# Rover-1_Power_Supply.net
KiCad netlist of a schematic drawn in EAGLE
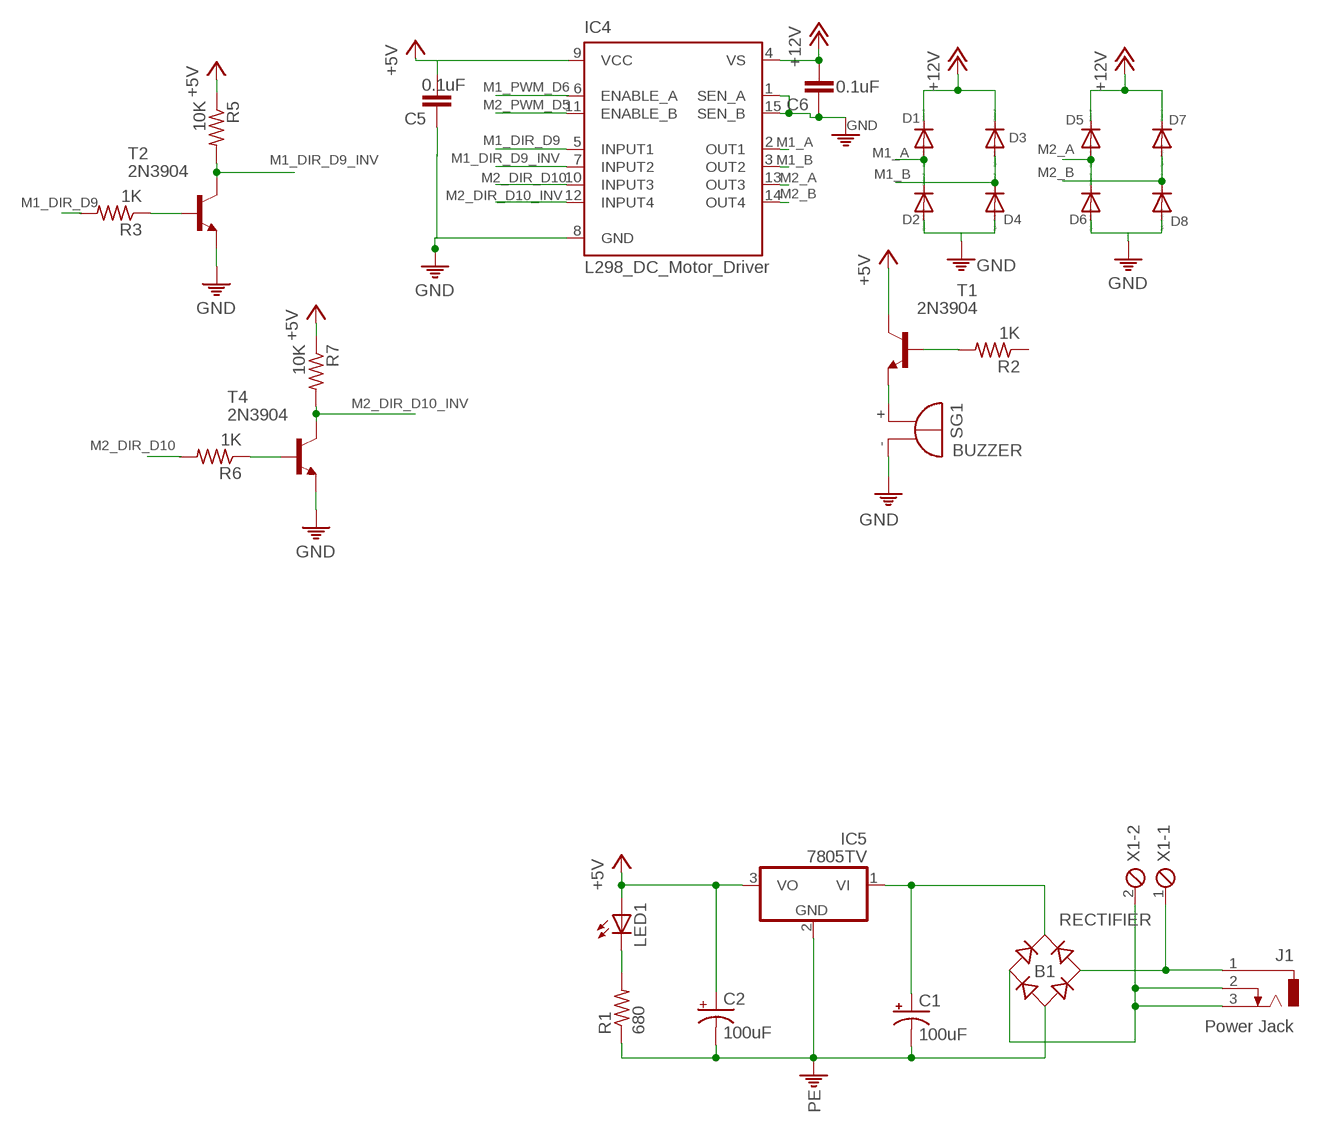
[diagram p0: schematic, sheet 1]

(export (version "E")
  (design (tool "Eeschema 10.0.6"))
  (components
    (comp (ref "B1")
      (value "RECTIFIER")
      (footprint "eagle-import:RB1A")
      (libsource (lib "eagle-import") (part "RB1A"))
    )
    (comp (ref "C1")
      (value "100uF")
      (footprint "eagle-import:E5-8,5")
      (libsource (lib "eagle-import") (part "CPOL-USE5-8.5"))
    )
    (comp (ref "C2")
      (value "100uF")
      (footprint "eagle-import:E5-8,5")
      (libsource (lib "eagle-import") (part "CPOL-USE5-8.5"))
    )
    (comp (ref "C5")
      (value "0.1uF")
      (footprint "eagle-import:C025-024X044")
      (libsource (lib "eagle-import") (part "C-EU025-024X044"))
    )
    (comp (ref "C6")
      (value "0.1uF")
      (footprint "eagle-import:C025-024X044")
      (libsource (lib "eagle-import") (part "C-EU025-024X044"))
    )
    (comp (ref "D1")
      (value "DIODE-D-2.5")
      (footprint "eagle-import:D-2.5")
      (libsource (lib "eagle-import") (part "DIODE-D-2.5"))
    )
    (comp (ref "D2")
      (value "DIODE-D-2.5")
      (footprint "eagle-import:D-2.5")
      (libsource (lib "eagle-import") (part "DIODE-D-2.5"))
    )
    (comp (ref "D3")
      (value "DIODE-D-2.5")
      (footprint "eagle-import:D-2.5")
      (libsource (lib "eagle-import") (part "DIODE-D-2.5"))
    )
    (comp (ref "D4")
      (value "DIODE-D-2.5")
      (footprint "eagle-import:D-2.5")
      (libsource (lib "eagle-import") (part "DIODE-D-2.5"))
    )
    (comp (ref "D5")
      (value "DIODE-D-2.5")
      (footprint "eagle-import:D-2.5")
      (libsource (lib "eagle-import") (part "DIODE-D-2.5"))
    )
    (comp (ref "D6")
      (value "DIODE-D-2.5")
      (footprint "eagle-import:D-2.5")
      (libsource (lib "eagle-import") (part "DIODE-D-2.5"))
    )
    (comp (ref "D7")
      (value "DIODE-D-2.5")
      (footprint "eagle-import:D-2.5")
      (libsource (lib "eagle-import") (part "DIODE-D-2.5"))
    )
    (comp (ref "D8")
      (value "DIODE-D-2.5")
      (footprint "eagle-import:D-2.5")
      (libsource (lib "eagle-import") (part "DIODE-D-2.5"))
    )
    (comp (ref "IC4")
      (value "L298_DC_Motor_Driver")
      (footprint "eagle-import:MULTIWATT-15")
      (fields (field (name "MPN") "L298N"))
      (libsource (lib "eagle-import") (part "L298"))
    )
    (comp (ref "IC5")
      (value "7805TV")
      (footprint "eagle-import:TO220V")
      (libsource (lib "eagle-import") (part "78TV05"))
    )
    (comp (ref "J1")
      (value "Power Jack")
      (footprint "eagle-import:ROVER-PW-JACL")
      (libsource (lib "eagle-import") (part "DCJ0303"))
    )
    (comp (ref "LED1")
      (value "LED3MM")
      (footprint "eagle-import:LED3MM")
      (libsource (lib "eagle-import") (part "LED3MM"))
    )
    (comp (ref "R1")
      (value "680")
      (footprint "eagle-import:0204_5")
      (libsource (lib "eagle-import") (part "R-US_0204/5"))
    )
    (comp (ref "R2")
      (value "1K")
      (footprint "eagle-import:0204_5")
      (libsource (lib "eagle-import") (part "R-US_0204/5"))
    )
    (comp (ref "R3")
      (value "1K")
      (footprint "eagle-import:0204_5")
      (libsource (lib "eagle-import") (part "R-US_0204/5"))
    )
    (comp (ref "R5")
      (value "10K")
      (footprint "eagle-import:0204_5")
      (libsource (lib "eagle-import") (part "R-US_0204/5"))
    )
    (comp (ref "R6")
      (value "1K")
      (footprint "eagle-import:0204_5")
      (libsource (lib "eagle-import") (part "R-US_0204/5"))
    )
    (comp (ref "R7")
      (value "10K")
      (footprint "eagle-import:0204_5")
      (libsource (lib "eagle-import") (part "R-US_0204/5"))
    )
    (comp (ref "SG1")
      (value "BUZZER")
      (footprint "eagle-import:EB2209A")
      (libsource (lib "eagle-import") (part "EB2209A"))
    )
    (comp (ref "T1")
      (value "2N3904")
      (footprint "eagle-import:TO92")
      (libsource (lib "eagle-import") (part "2N3904"))
    )
    (comp (ref "T2")
      (value "2N3904")
      (footprint "eagle-import:TO92")
      (libsource (lib "eagle-import") (part "2N3904"))
    )
    (comp (ref "T4")
      (value "2N3904")
      (footprint "eagle-import:TO92")
      (libsource (lib "eagle-import") (part "2N3904"))
    )
    (comp (ref "X1")
      (value "MPT2")
      (footprint "eagle-import:2POL254")
      (libsource (lib "eagle-import") (part "MPT2"))
    )
  )
  (nets
    (net (code "1") (name "+5V") (class "Default")
      (node (ref "C2") (pin "+") (pinfunction "+_+") (pintype "passive"))
      (node (ref "C5") (pin "2") (pinfunction "2_2") (pintype "passive"))
      (node (ref "IC5") (pin "3") (pinfunction "VO_3") (pintype "passive"))
      (node (ref "LED1") (pin "A") (pinfunction "A_A") (pintype "passive"))
      (node (ref "R5") (pin "1") (pinfunction "1_1") (pintype "passive"))
      (node (ref "R7") (pin "1") (pinfunction "1_1") (pintype "passive"))
      (node (ref "T1") (pin "1") (pinfunction "C_1") (pintype "passive"))
    )
    (net (code "2") (name "+12V") (class "Default")
      (node (ref "C6") (pin "2") (pinfunction "2_2") (pintype "passive"))
      (node (ref "D1") (pin "C") (pinfunction "C_C") (pintype "passive"))
      (node (ref "D3") (pin "C") (pinfunction "C_C") (pintype "passive"))
      (node (ref "D5") (pin "C") (pinfunction "C_C") (pintype "passive"))
      (node (ref "D7") (pin "C") (pinfunction "C_C") (pintype "passive"))
      (node (ref "IC4") (pin "4") (pinfunction "VS_4") (pintype "power_in"))
    )
    (net (code "3") (name "/M1_A") (class "Default")
      (node (ref "D1") (pin "A") (pinfunction "A_A") (pintype "passive"))
      (node (ref "D2") (pin "C") (pinfunction "C_C") (pintype "passive"))
      (node (ref "IC4") (pin "2") (pinfunction "OUT1_2") (pintype "output"))
    )
    (net (code "4") (name "/M1_B") (class "Default")
      (node (ref "D3") (pin "A") (pinfunction "A_A") (pintype "passive"))
      (node (ref "D4") (pin "C") (pinfunction "C_C") (pintype "passive"))
      (node (ref "IC4") (pin "3") (pinfunction "OUT2_3") (pintype "output"))
    )
    (net (code "5") (name "/M1_DIR_D9") (class "Default")
      (node (ref "IC4") (pin "5") (pinfunction "INPUT1_5") (pintype "input"))
    )
    (net (code "6") (name "/M1_DIR_D9_INV") (class "Default")
      (node (ref "IC4") (pin "7") (pinfunction "INPUT2_7") (pintype "input"))
      (node (ref "R5") (pin "2") (pinfunction "2_2") (pintype "passive"))
      (node (ref "T2") (pin "1") (pinfunction "C_1") (pintype "passive"))
    )
    (net (code "8") (name "/M2_A") (class "Default")
      (node (ref "D5") (pin "A") (pinfunction "A_A") (pintype "passive"))
      (node (ref "D6") (pin "C") (pinfunction "C_C") (pintype "passive"))
      (node (ref "IC4") (pin "13") (pinfunction "OUT3_13") (pintype "output"))
    )
    (net (code "9") (name "/M2_B") (class "Default")
      (node (ref "D7") (pin "A") (pinfunction "A_A") (pintype "passive"))
      (node (ref "D8") (pin "C") (pinfunction "C_C") (pintype "passive"))
      (node (ref "IC4") (pin "14") (pinfunction "OUT4_14") (pintype "output"))
    )
    (net (code "10") (name "/M2_DIR_D10") (class "Default")
      (node (ref "IC4") (pin "10") (pinfunction "INPUT3_10") (pintype "input"))
    )
    (net (code "11") (name "/M2_DIR_D10_INV") (class "Default")
      (node (ref "IC4") (pin "12") (pinfunction "INPUT4_12") (pintype "input"))
      (node (ref "R7") (pin "2") (pinfunction "2_2") (pintype "passive"))
      (node (ref "T4") (pin "1") (pinfunction "C_1") (pintype "passive"))
    )
    (net (code "12") (name "/M2_PWM_D5") (class "Default")
      (node (ref "IC4") (pin "11") (pinfunction "ENABLE_B_11") (pintype "input"))
    )
    (net (code "13") (name "/VCC") (class "Default")
      (node (ref "IC4") (pin "9") (pinfunction "VCC_9") (pintype "power_in"))
    )
    (net (code "14") (name "GND") (class "Default")
      (node (ref "B1") (pin "-") (pinfunction "-_-") (pintype "passive"))
      (node (ref "C1") (pin "-") (pinfunction "-_-") (pintype "passive"))
      (node (ref "C2") (pin "-") (pinfunction "-_-") (pintype "passive"))
      (node (ref "C6") (pin "1") (pinfunction "1_1") (pintype "passive"))
      (node (ref "D2") (pin "A") (pinfunction "A_A") (pintype "passive"))
      (node (ref "D4") (pin "A") (pinfunction "A_A") (pintype "passive"))
      (node (ref "D6") (pin "A") (pinfunction "A_A") (pintype "passive"))
      (node (ref "D8") (pin "A") (pinfunction "A_A") (pintype "passive"))
      (node (ref "IC4") (pin "1") (pinfunction "SEN_A_1") (pintype "input"))
      (node (ref "IC4") (pin "15") (pinfunction "SEN_B_15") (pintype "input"))
      (node (ref "IC4") (pin "8") (pinfunction "GND_8") (pintype "power_in"))
      (node (ref "IC5") (pin "2") (pinfunction "GND_2") (pintype "passive"))
      (node (ref "R1") (pin "1") (pinfunction "1_1") (pintype "passive"))
      (node (ref "SG1") (pin "-") (pinfunction "-_-") (pintype "passive"))
      (node (ref "T2") (pin "3") (pinfunction "E_3") (pintype "passive"))
      (node (ref "T4") (pin "3") (pinfunction "E_3") (pintype "passive"))
    )
    (net (code "15") (name "Net-(B1-PadAC1)") (class "Default")
      (node (ref "B1") (pin "AC1") (pinfunction "AC1_AC1") (pintype "passive"))
      (node (ref "J1") (pin "1") (pinfunction "1_1") (pintype "passive"))
      (node (ref "X1") (pin "1") (pinfunction "1_1") (pintype "passive"))
    )
    (net (code "16") (name "Net-(IC5-VI)") (class "Default")
      (node (ref "B1") (pin "+") (pinfunction "+_+") (pintype "passive"))
      (node (ref "C1") (pin "+") (pinfunction "+_+") (pintype "passive"))
      (node (ref "IC5") (pin "1") (pinfunction "VI_1") (pintype "input"))
    )
    (net (code "17") (name "Net-(LED1-C)") (class "Default")
      (node (ref "LED1") (pin "K") (pinfunction "C_K") (pintype "passive"))
      (node (ref "R1") (pin "2") (pinfunction "2_2") (pintype "passive"))
    )
    (net (code "18") (name "Net-(T1-E)") (class "Default")
      (node (ref "SG1") (pin "+") (pinfunction "+_+") (pintype "passive"))
      (node (ref "T1") (pin "3") (pinfunction "E_3") (pintype "passive"))
    )
    (net (code "19") (name "Net-(T2-B)") (class "Default")
      (node (ref "R3") (pin "1") (pinfunction "1_1") (pintype "passive"))
      (node (ref "T2") (pin "2") (pinfunction "B_2") (pintype "passive"))
    )
    (net (code "20") (name "Net-(T4-B)") (class "Default")
      (node (ref "R6") (pin "1") (pinfunction "1_1") (pintype "passive"))
      (node (ref "T4") (pin "2") (pinfunction "B_2") (pintype "passive"))
    )
    (net (code "21") (name "Net-(X1B-1)") (class "Default")
      (node (ref "B1") (pin "AC2") (pinfunction "AC2_AC2") (pintype "passive"))
      (node (ref "J1") (pin "2") (pinfunction "2_2") (pintype "passive"))
      (node (ref "J1") (pin "3") (pinfunction "3_3") (pintype "passive"))
      (node (ref "X1") (pin "2") (pinfunction "1_2") (pintype "passive"))
    )
    (net (code "22") (name "unconnected-(C5-Pad1)") (class "Default")
      (node (ref "C5") (pin "1") (pinfunction "1_1") (pintype "passive"))
    )
    (net (code "23") (name "unconnected-(IC4-ENABLE_A-Pad6)") (class "Default")
      (node (ref "IC4") (pin "6") (pinfunction "ENABLE_A_6") (pintype "input"))
    )
    (net (code "24") (name "unconnected-(R2-Pad1)") (class "Default")
      (node (ref "R2") (pin "1") (pinfunction "1_1") (pintype "passive"))
    )
    (net (code "25") (name "unconnected-(R2-Pad2)") (class "Default")
      (node (ref "R2") (pin "2") (pinfunction "2_2") (pintype "passive"))
    )
    (net (code "26") (name "unconnected-(R3-Pad2)") (class "Default")
      (node (ref "R3") (pin "2") (pinfunction "2_2") (pintype "passive"))
    )
    (net (code "27") (name "unconnected-(R6-Pad2)") (class "Default")
      (node (ref "R6") (pin "2") (pinfunction "2_2") (pintype "passive"))
    )
    (net (code "28") (name "unconnected-(T1-B-Pad2)") (class "Default")
      (node (ref "T1") (pin "2") (pinfunction "B_2") (pintype "passive"))
    )
  )
)
